# Voice_Interaction_Hat_for_raspberry_pi_v.net
KiCad netlist of a schematic drawn in EAGLE
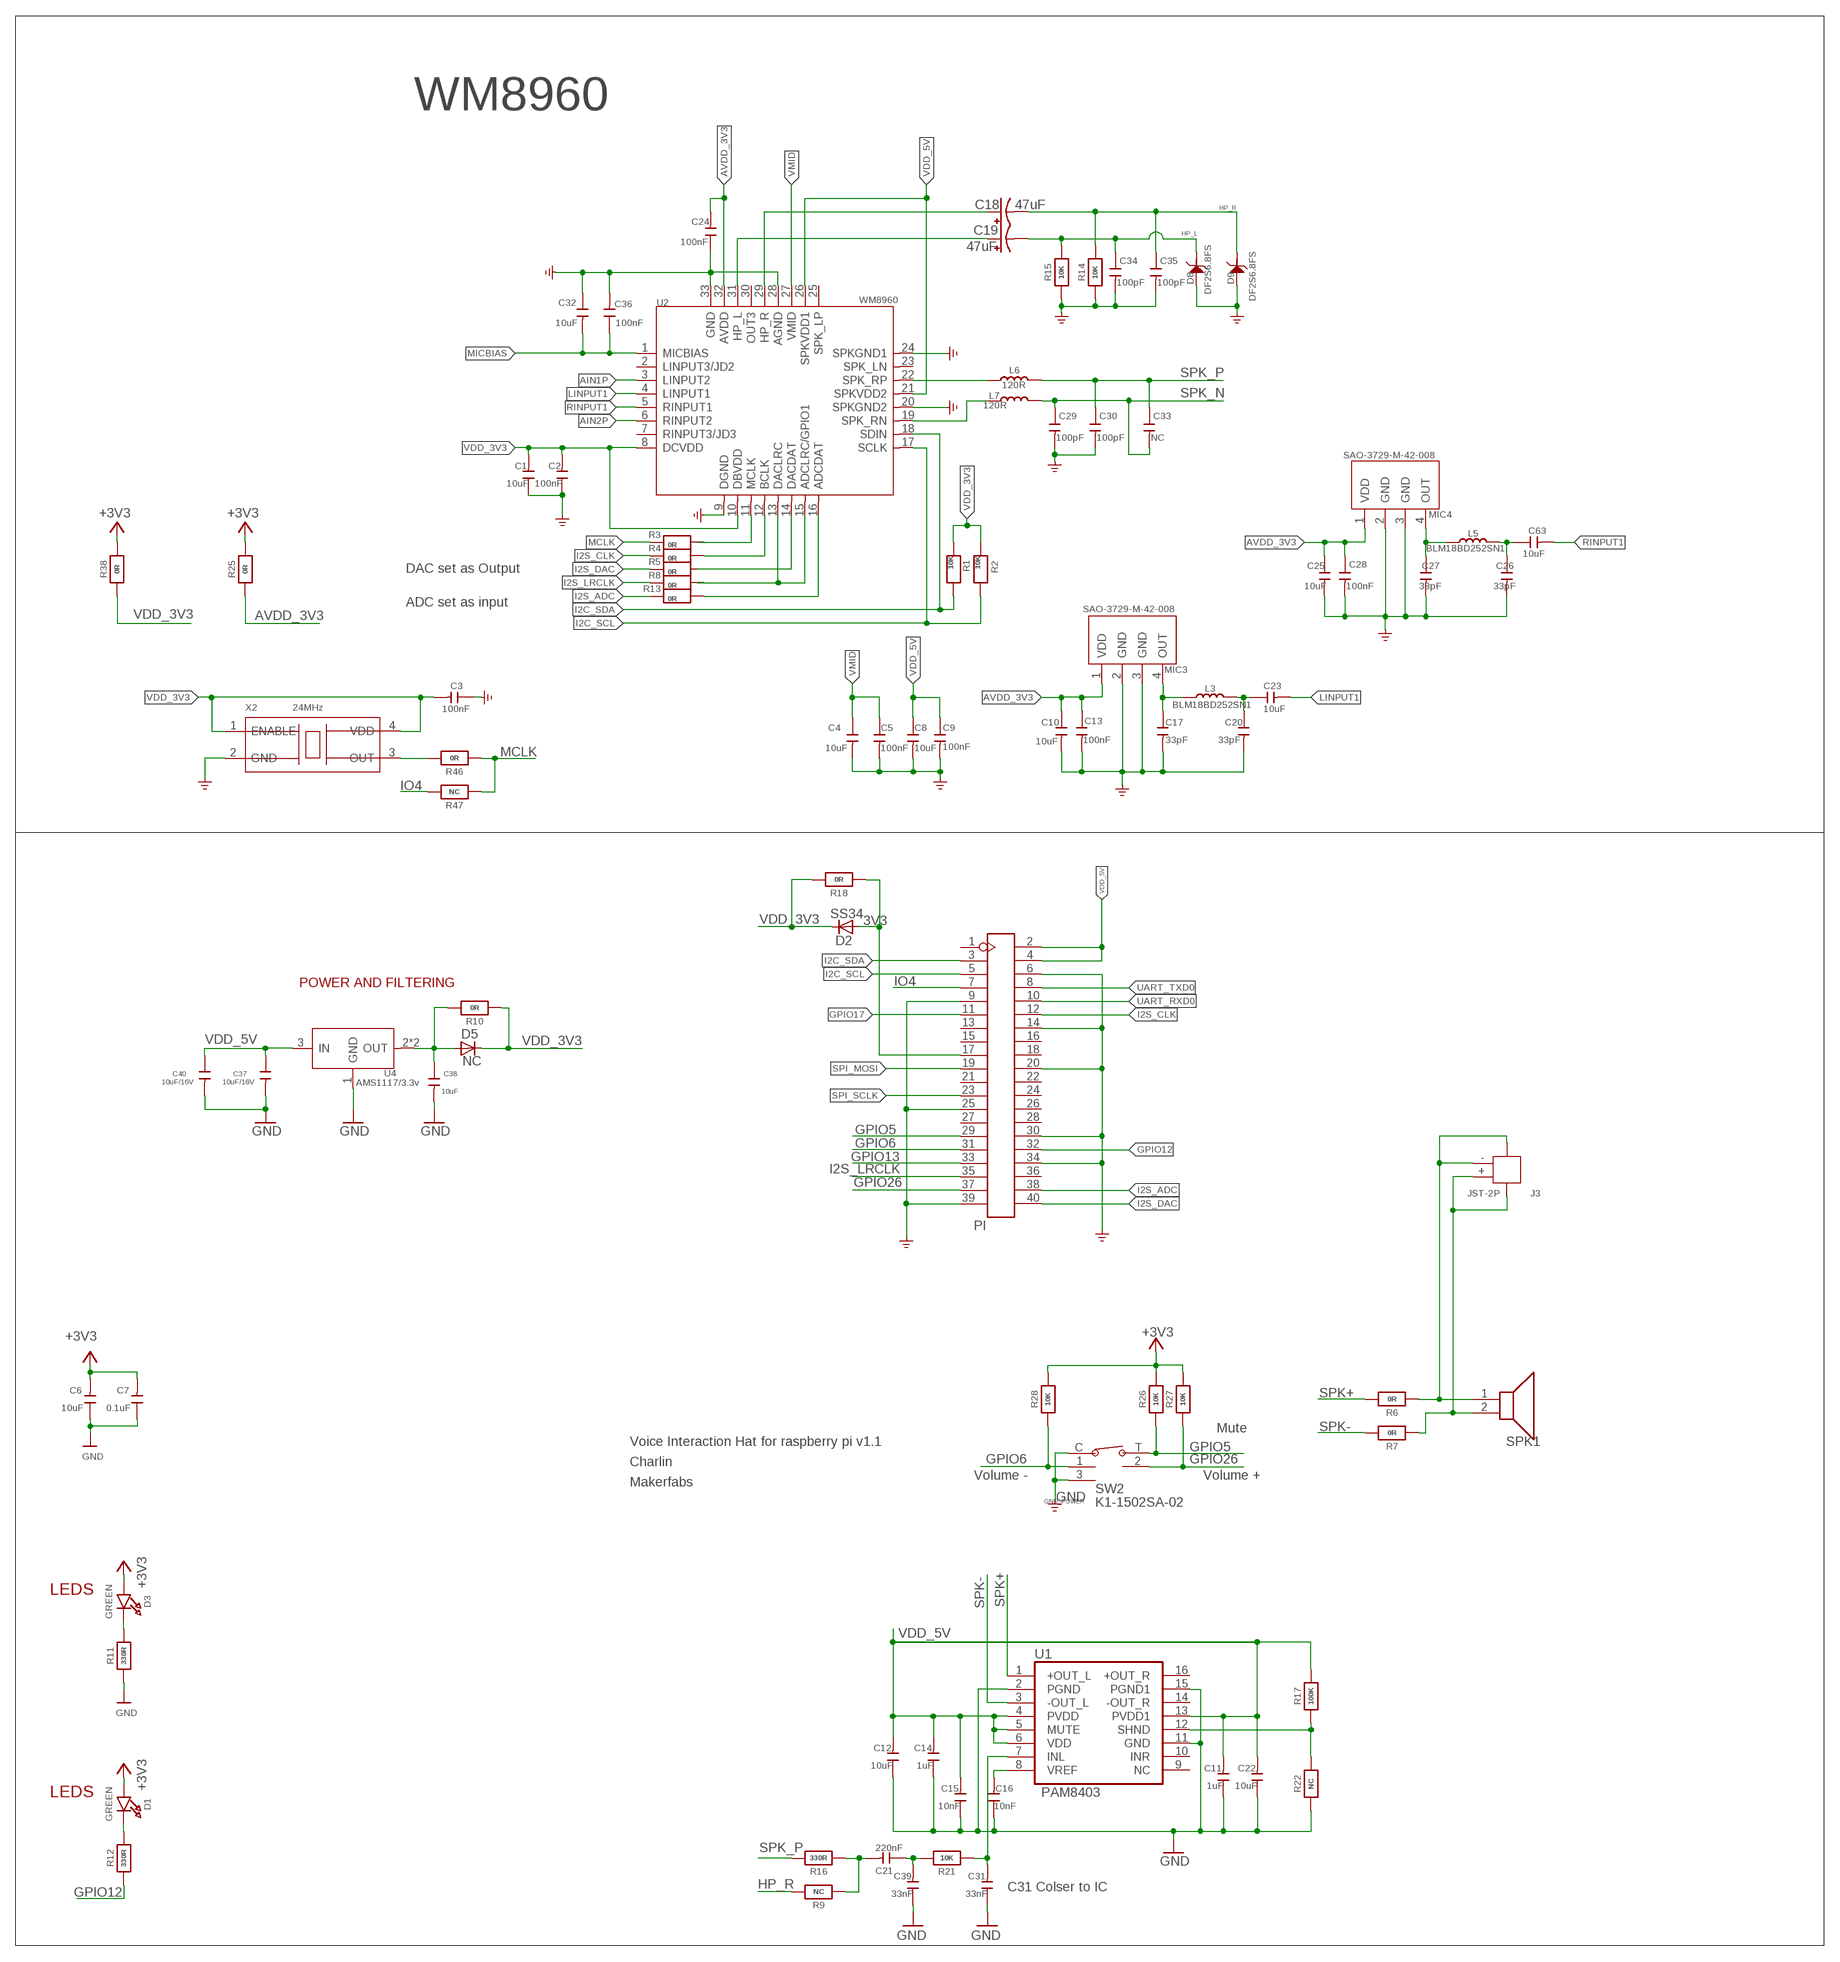
[diagram p0: schematic, sheet 1]

(export (version "E")
  (design (tool "Eeschema 10.0.6"))
  (components
    (comp (ref "C1")
      (value "10uF")
      (footprint "eagle-import:DISCRETE_C0603")
      (libsource (lib "eagle-import") (part "DISCRETE_C-0603"))
    )
    (comp (ref "C2")
      (value "100nF")
      (footprint "eagle-import:DISCRETE_C0603")
      (libsource (lib "eagle-import") (part "DISCRETE_C-0603"))
    )
    (comp (ref "C3")
      (value "100nF")
      (footprint "eagle-import:DISCRETE_C0603")
      (libsource (lib "eagle-import") (part "DISCRETE_C-0603"))
    )
    (comp (ref "C4")
      (value "10uF")
      (footprint "eagle-import:C0603")
      (libsource (lib "eagle-import") (part "CAP-0603"))
    )
    (comp (ref "C5")
      (value "100nF")
      (footprint "eagle-import:C0603")
      (libsource (lib "eagle-import") (part "CAP-0603"))
    )
    (comp (ref "C6")
      (value "10uF")
      (footprint "eagle-import:DISCRETE_C0603")
      (libsource (lib "eagle-import") (part "DISCRETE_C-0603"))
    )
    (comp (ref "C7")
      (value "0.1uF")
      (footprint "eagle-import:DISCRETE_C0603")
      (libsource (lib "eagle-import") (part "DISCRETE_C-0603"))
    )
    (comp (ref "C8")
      (value "10uF")
      (footprint "eagle-import:C0603")
      (libsource (lib "eagle-import") (part "CAP-0603"))
    )
    (comp (ref "C9")
      (value "100nF")
      (footprint "eagle-import:C0603")
      (libsource (lib "eagle-import") (part "CAP-0603"))
    )
    (comp (ref "C10")
      (value "10uF")
      (footprint "eagle-import:C0603")
      (libsource (lib "eagle-import") (part "CAP-0603"))
    )
    (comp (ref "C11")
      (value "1uF")
      (footprint "eagle-import:DISCRETE_C0603")
      (libsource (lib "eagle-import") (part "DISCRETE_C-0603"))
    )
    (comp (ref "C12")
      (value "10uF")
      (footprint "eagle-import:DISCRETE_C0603")
      (libsource (lib "eagle-import") (part "DISCRETE_C-0603"))
    )
    (comp (ref "C13")
      (value "100nF")
      (footprint "eagle-import:C0603")
      (libsource (lib "eagle-import") (part "CAP-0603"))
    )
    (comp (ref "C14")
      (value "1uF")
      (footprint "eagle-import:DISCRETE_C0603")
      (libsource (lib "eagle-import") (part "DISCRETE_C-0603"))
    )
    (comp (ref "C15")
      (value "10nF")
      (footprint "eagle-import:DISCRETE_C0603")
      (libsource (lib "eagle-import") (part "DISCRETE_C-0603"))
    )
    (comp (ref "C16")
      (value "10nF")
      (footprint "eagle-import:DISCRETE_C0603")
      (libsource (lib "eagle-import") (part "DISCRETE_C-0603"))
    )
    (comp (ref "C17")
      (value "33pF")
      (footprint "eagle-import:C0603")
      (libsource (lib "eagle-import") (part "CAP-0603"))
    )
    (comp (ref "C18")
      (value "47uF")
      (footprint "eagle-import:EIA3528")
      (libsource (lib "eagle-import") (part "47UF-POLAR-EIA3528-10V-10%"))
    )
    (comp (ref "C19")
      (value "47uF")
      (footprint "eagle-import:EIA3528")
      (libsource (lib "eagle-import") (part "47UF-POLAR-EIA3528-10V-10%"))
    )
    (comp (ref "C20")
      (value "33pF")
      (footprint "eagle-import:C0603")
      (libsource (lib "eagle-import") (part "CAP-0603"))
    )
    (comp (ref "C21")
      (value "220nF")
      (footprint "eagle-import:DISCRETE_C0603")
      (libsource (lib "eagle-import") (part "DISCRETE_C-0603"))
    )
    (comp (ref "C22")
      (value "10uF")
      (footprint "eagle-import:DISCRETE_C0603")
      (libsource (lib "eagle-import") (part "DISCRETE_C-0603"))
    )
    (comp (ref "C23")
      (value "10uF")
      (footprint "eagle-import:C0603")
      (libsource (lib "eagle-import") (part "CAP-0603"))
    )
    (comp (ref "C24")
      (value "100nF")
      (footprint "eagle-import:DISCRETE_C0603")
      (libsource (lib "eagle-import") (part "DISCRETE_C-0603"))
    )
    (comp (ref "C25")
      (value "10uF")
      (footprint "eagle-import:C0603")
      (libsource (lib "eagle-import") (part "CAP-0603"))
    )
    (comp (ref "C26")
      (value "33pF")
      (footprint "eagle-import:C0603")
      (libsource (lib "eagle-import") (part "CAP-0603"))
    )
    (comp (ref "C27")
      (value "33pF")
      (footprint "eagle-import:C0603")
      (libsource (lib "eagle-import") (part "CAP-0603"))
    )
    (comp (ref "C28")
      (value "100nF")
      (footprint "eagle-import:C0603")
      (libsource (lib "eagle-import") (part "CAP-0603"))
    )
    (comp (ref "C29")
      (value "100pF")
      (footprint "eagle-import:C0603")
      (libsource (lib "eagle-import") (part "CAP-0603"))
    )
    (comp (ref "C30")
      (value "100pF")
      (footprint "eagle-import:C0603")
      (libsource (lib "eagle-import") (part "CAP-0603"))
    )
    (comp (ref "C31")
      (value "33nF")
      (footprint "eagle-import:DISCRETE_C0603")
      (libsource (lib "eagle-import") (part "DISCRETE_C-0603"))
    )
    (comp (ref "C32")
      (value "10uF")
      (footprint "eagle-import:C0603")
      (libsource (lib "eagle-import") (part "CAP-0603"))
    )
    (comp (ref "C33")
      (value "NC")
      (footprint "eagle-import:C0603")
      (libsource (lib "eagle-import") (part "CAP-0603"))
    )
    (comp (ref "C34")
      (value "100pF")
      (footprint "eagle-import:C0603")
      (libsource (lib "eagle-import") (part "CAP-0603"))
    )
    (comp (ref "C35")
      (value "100pF")
      (footprint "eagle-import:C0603")
      (libsource (lib "eagle-import") (part "CAP-0603"))
    )
    (comp (ref "C36")
      (value "100nF")
      (footprint "eagle-import:DISCRETE_C0603")
      (libsource (lib "eagle-import") (part "DISCRETE_C-0603"))
    )
    (comp (ref "C37")
      (value "10uF/16V")
      (footprint "eagle-import:0603")
      (libsource (lib "eagle-import") (part "C-0603"))
    )
    (comp (ref "C38")
      (value "10uF")
      (footprint "eagle-import:0603")
      (libsource (lib "eagle-import") (part "C-0603"))
    )
    (comp (ref "C39")
      (value "33nF")
      (footprint "eagle-import:DISCRETE_C0603")
      (libsource (lib "eagle-import") (part "DISCRETE_C-0603"))
    )
    (comp (ref "C40")
      (value "10uF/16V")
      (footprint "eagle-import:0603")
      (libsource (lib "eagle-import") (part "C-0603"))
    )
    (comp (ref "C63")
      (value "10uF")
      (footprint "eagle-import:C0603")
      (libsource (lib "eagle-import") (part "CAP-0603"))
    )
    (comp (ref "D1")
      (value "GREEN")
      (footprint "eagle-import:CHIPLED_0805_NOOUTLINE")
      (libsource (lib "eagle-import") (part "LED0805_NOOUTLINE"))
    )
    (comp (ref "D2")
      (value "SS34")
      (footprint "eagle-import:DO-214AC")
      (libsource (lib "eagle-import") (part "DIODE-DO-214AC"))
    )
    (comp (ref "D3")
      (value "GREEN")
      (footprint "eagle-import:CHIPLED_0805_NOOUTLINE")
      (libsource (lib "eagle-import") (part "LED0805_NOOUTLINE"))
    )
    (comp (ref "D5")
      (value "NC")
      (footprint "eagle-import:DO-214AC")
      (libsource (lib "eagle-import") (part "DIODE-DO-214AC"))
    )
    (comp (ref "D8")
      (value "DF2S6.8FS")
      (footprint "eagle-import:SOD-923")
      (libsource (lib "eagle-import") (part "D-ESD-2P'DF2S6.8FS'"))
    )
    (comp (ref "D9")
      (value "DF2S6.8FS")
      (footprint "eagle-import:SOD-923")
      (libsource (lib "eagle-import") (part "D-ESD-2P'DF2S6.8FS'"))
    )
    (comp (ref "J3")
      (value "JST-2P")
      (footprint "eagle-import:HW2-SMD-2.0-90D")
      (libsource (lib "eagle-import") (part "JST-2P-SMD'2.0'"))
    )
    (comp (ref "L3")
      (value "BLM18BD252SN1")
      (footprint "eagle-import:L0603")
      (libsource (lib "eagle-import") (part "INDUCTOR/FERRITE-BEAD'0603'"))
    )
    (comp (ref "L5")
      (value "BLM18BD252SN1")
      (footprint "eagle-import:L0603")
      (libsource (lib "eagle-import") (part "INDUCTOR/FERRITE-BEAD'0603'"))
    )
    (comp (ref "L6")
      (value "120R")
      (footprint "eagle-import:L0603")
      (libsource (lib "eagle-import") (part "INDUCTOR/FERRITE-BEAD'0603'"))
    )
    (comp (ref "L7")
      (value "120R")
      (footprint "eagle-import:L0603")
      (libsource (lib "eagle-import") (part "INDUCTOR/FERRITE-BEAD'0603'"))
    )
    (comp (ref "MIC3")
      (value "SAO-3729-M-42-008")
      (footprint "eagle-import:MIC4-SMD-3.76X2.95MM")
      (libsource (lib "eagle-import") (part "MIC-MSM421A3729H8-C"))
    )
    (comp (ref "MIC4")
      (value "SAO-3729-M-42-008")
      (footprint "eagle-import:MIC4-SMD-3.76X2.95MM")
      (libsource (lib "eagle-import") (part "MIC-MSM421A3729H8-C"))
    )
    (comp (ref "PI")
      (value "HEADER-2X20P1")
      (footprint "eagle-import:DIP-2X20-2.54MM")
      (libsource (lib "eagle-import") (part "HEADER-2X20P1"))
    )
    (comp (ref "R1")
      (value "10K")
      (footprint "eagle-import:0603-NO")
      (libsource (lib "eagle-import") (part "RESISTOR_0603_NOOUT"))
    )
    (comp (ref "R2")
      (value "10K")
      (footprint "eagle-import:0603-NO")
      (libsource (lib "eagle-import") (part "RESISTOR_0603_NOOUT"))
    )
    (comp (ref "R3")
      (value "0R")
      (footprint "eagle-import:0603-NO")
      (libsource (lib "eagle-import") (part "RESISTOR_0603_NOOUT"))
    )
    (comp (ref "R4")
      (value "0R")
      (footprint "eagle-import:0603-NO")
      (libsource (lib "eagle-import") (part "RESISTOR_0603_NOOUT"))
    )
    (comp (ref "R5")
      (value "0R")
      (footprint "eagle-import:0603-NO")
      (libsource (lib "eagle-import") (part "RESISTOR_0603_NOOUT"))
    )
    (comp (ref "R6")
      (value "0R")
      (footprint "eagle-import:0603-NO")
      (libsource (lib "eagle-import") (part "RESISTOR_0603_NOOUT"))
    )
    (comp (ref "R7")
      (value "0R")
      (footprint "eagle-import:0603-NO")
      (libsource (lib "eagle-import") (part "RESISTOR_0603_NOOUT"))
    )
    (comp (ref "R8")
      (value "0R")
      (footprint "eagle-import:0603-NO")
      (libsource (lib "eagle-import") (part "RESISTOR_0603_NOOUT"))
    )
    (comp (ref "R9")
      (value "NC")
      (footprint "eagle-import:0603-NO")
      (libsource (lib "eagle-import") (part "RESISTOR_0603_NOOUT"))
    )
    (comp (ref "R10")
      (value "0R")
      (footprint "eagle-import:0603-NO")
      (libsource (lib "eagle-import") (part "RESISTOR_0603_NOOUT"))
    )
    (comp (ref "R11")
      (value "330R")
      (footprint "eagle-import:0603-NO")
      (libsource (lib "eagle-import") (part "RESISTOR_0603_NOOUT"))
    )
    (comp (ref "R12")
      (value "330R")
      (footprint "eagle-import:0603-NO")
      (libsource (lib "eagle-import") (part "RESISTOR_0603_NOOUT"))
    )
    (comp (ref "R13")
      (value "0R")
      (footprint "eagle-import:0603-NO")
      (libsource (lib "eagle-import") (part "RESISTOR_0603_NOOUT"))
    )
    (comp (ref "R14")
      (value "10K")
      (footprint "eagle-import:0603-NO")
      (libsource (lib "eagle-import") (part "RESISTOR_0603_NOOUT"))
    )
    (comp (ref "R15")
      (value "10K")
      (footprint "eagle-import:0603-NO")
      (libsource (lib "eagle-import") (part "RESISTOR_0603_NOOUT"))
    )
    (comp (ref "R16")
      (value "330R")
      (footprint "eagle-import:0603-NO")
      (libsource (lib "eagle-import") (part "RESISTOR_0603_NOOUT"))
    )
    (comp (ref "R17")
      (value "100K")
      (footprint "eagle-import:0603-NO")
      (libsource (lib "eagle-import") (part "RESISTOR_0603_NOOUT"))
    )
    (comp (ref "R18")
      (value "0R")
      (footprint "eagle-import:0603-NO")
      (libsource (lib "eagle-import") (part "RESISTOR_0603_NOOUT"))
    )
    (comp (ref "R21")
      (value "10K")
      (footprint "eagle-import:0603-NO")
      (libsource (lib "eagle-import") (part "RESISTOR_0603_NOOUT"))
    )
    (comp (ref "R22")
      (value "NC")
      (footprint "eagle-import:0603-NO")
      (libsource (lib "eagle-import") (part "RESISTOR_0603_NOOUT"))
    )
    (comp (ref "R25")
      (value "0R")
      (footprint "eagle-import:0603-NO")
      (libsource (lib "eagle-import") (part "RESISTOR_0603_NOOUT"))
    )
    (comp (ref "R26")
      (value "10K")
      (footprint "eagle-import:0603-NO")
      (libsource (lib "eagle-import") (part "RESISTOR_0603_NOOUT"))
    )
    (comp (ref "R27")
      (value "10K")
      (footprint "eagle-import:0603-NO")
      (libsource (lib "eagle-import") (part "RESISTOR_0603_NOOUT"))
    )
    (comp (ref "R28")
      (value "10K")
      (footprint "eagle-import:0603-NO")
      (libsource (lib "eagle-import") (part "RESISTOR_0603_NOOUT"))
    )
    (comp (ref "R38")
      (value "0R")
      (footprint "eagle-import:0603-NO")
      (libsource (lib "eagle-import") (part "RESISTOR_0603_NOOUT"))
    )
    (comp (ref "R46")
      (value "0R")
      (footprint "eagle-import:0603-NO")
      (libsource (lib "eagle-import") (part "RESISTOR_0603_NOOUT"))
    )
    (comp (ref "R47")
      (value "NC")
      (footprint "eagle-import:0603-NO")
      (libsource (lib "eagle-import") (part "RESISTOR_0603_NOOUT"))
    )
    (comp (ref "SPK1")
      (value "SPK")
      (footprint "eagle-import:SPK-SMD2-5000L3000W")
      (libsource (lib "eagle-import") (part "SPK"))
    )
    (comp (ref "SW2")
      (value "K1-1502SA-02")
      (footprint "eagle-import:SMD5-60P-1180L1170W")
      (libsource (lib "eagle-import") (part "K1-1502SA-02"))
    )
    (comp (ref "U1")
      (value "PAM8403")
      (footprint "eagle-import:SOP-16")
      (libsource (lib "eagle-import") (part "PAM8403"))
    )
    (comp (ref "U2")
      (value "WM8960")
      (footprint "eagle-import:QFN32G-0.5-5X5MM")
      (libsource (lib "eagle-import") (part "AMPLIFIER-WM8960"))
    )
    (comp (ref "U4")
      (value "AMS1117/3.3v")
      (footprint "eagle-import:SOT89")
      (libsource (lib "eagle-import") (part "LD1117'SOT89'"))
    )
    (comp (ref "X2")
      (value "24MHz")
      (footprint "eagle-import:OSC4-SMD-2.5X2.0X0.8MM")
      (libsource (lib "eagle-import") (part "CRYSTAL-OSCILLATOR2.52.0"))
    )
  )
  (nets
    (net (code "1") (name "+3V3") (class "Default")
      (node (ref "C6") (pin "2") (pinfunction "2_2") (pintype "passive"))
      (node (ref "C7") (pin "2") (pinfunction "2_2") (pintype "passive"))
      (node (ref "D1") (pin "A") (pinfunction "A_A") (pintype "passive"))
      (node (ref "D3") (pin "A") (pinfunction "A_A") (pintype "passive"))
      (node (ref "R25") (pin "2") (pinfunction "2_2") (pintype "passive"))
      (node (ref "R26") (pin "2") (pinfunction "2_2") (pintype "passive"))
      (node (ref "R27") (pin "2") (pinfunction "2_2") (pintype "passive"))
      (node (ref "R28") (pin "2") (pinfunction "2_2") (pintype "passive"))
      (node (ref "R38") (pin "2") (pinfunction "2_2") (pintype "passive"))
    )
    (net (code "2") (name "/3V3") (class "Default")
      (node (ref "D2") (pin "A") (pinfunction "A_A") (pintype "passive"))
      (node (ref "PI") (pin "17") (pinfunction "17_17") (pintype "bidirectional"))
      (node (ref "R18") (pin "1") (pinfunction "1_1") (pintype "passive"))
    )
    (net (code "3") (name "/GPIO5") (class "Default")
      (node (ref "PI") (pin "29") (pinfunction "29_29") (pintype "bidirectional"))
      (node (ref "R26") (pin "1") (pinfunction "1_1") (pintype "passive"))
      (node (ref "SW2") (pin "T") (pinfunction "T_T") (pintype "bidirectional"))
    )
    (net (code "4") (name "/GPIO6") (class "Default")
      (node (ref "PI") (pin "31") (pinfunction "31_31") (pintype "bidirectional"))
      (node (ref "R28") (pin "1") (pinfunction "1_1") (pintype "passive"))
      (node (ref "SW2") (pin "1") (pinfunction "1_1") (pintype "bidirectional"))
    )
    (net (code "5") (name "/GPIO13") (class "Default")
      (node (ref "PI") (pin "33") (pinfunction "33_33") (pintype "bidirectional"))
    )
    (net (code "6") (name "/GPIO26") (class "Default")
      (node (ref "PI") (pin "37") (pinfunction "37_37") (pintype "bidirectional"))
      (node (ref "R27") (pin "1") (pinfunction "1_1") (pintype "passive"))
      (node (ref "SW2") (pin "2") (pinfunction "2_2") (pintype "bidirectional"))
    )
    (net (code "7") (name "/HP_L") (class "Default")
      (node (ref "C19") (pin "C") (pinfunction "-_C") (pintype "passive"))
      (node (ref "C34") (pin "1") (pinfunction "1_1") (pintype "passive"))
      (node (ref "D8") (pin "1") (pinfunction "2_1") (pintype "bidirectional"))
      (node (ref "R15") (pin "2") (pinfunction "2_2") (pintype "passive"))
    )
    (net (code "8") (name "/HP_R") (class "Default")
      (node (ref "C18") (pin "C") (pinfunction "-_C") (pintype "passive"))
      (node (ref "C35") (pin "1") (pinfunction "1_1") (pintype "passive"))
      (node (ref "D9") (pin "1") (pinfunction "2_1") (pintype "bidirectional"))
      (node (ref "R14") (pin "2") (pinfunction "2_2") (pintype "passive"))
      (node (ref "R9") (pin "2") (pinfunction "2_2") (pintype "passive"))
    )
    (net (code "9") (name "/IO4") (class "Default")
      (node (ref "PI") (pin "7") (pinfunction "7_7") (pintype "bidirectional"))
      (node (ref "R47") (pin "2") (pinfunction "2_2") (pintype "passive"))
    )
    (net (code "10") (name "/SPK+") (class "Default")
      (node (ref "R6") (pin "2") (pinfunction "2_2") (pintype "passive"))
      (node (ref "U1") (pin "1") (pinfunction "+OUT_L_1") (pintype "input"))
    )
    (net (code "11") (name "/SPK-") (class "Default")
      (node (ref "R7") (pin "2") (pinfunction "2_2") (pintype "passive"))
      (node (ref "U1") (pin "3") (pinfunction "-OUT_L_3") (pintype "input"))
    )
    (net (code "12") (name "/SPK_N") (class "Default")
      (node (ref "C29") (pin "1") (pinfunction "1_1") (pintype "passive"))
      (node (ref "C33") (pin "2") (pinfunction "2_2") (pintype "passive"))
      (node (ref "L7") (pin "2") (pinfunction "2_2") (pintype "passive"))
    )
    (net (code "13") (name "/SPK_P") (class "Default")
      (node (ref "C30") (pin "1") (pinfunction "1_1") (pintype "passive"))
      (node (ref "C33") (pin "1") (pinfunction "1_1") (pintype "passive"))
      (node (ref "L6") (pin "2") (pinfunction "2_2") (pintype "passive"))
      (node (ref "R16") (pin "2") (pinfunction "2_2") (pintype "passive"))
    )
    (net (code "14") (name "AIN1P") (class "Default")
      (node (ref "U2") (pin "3") (pinfunction "LINPUT2_3") (pintype "bidirectional"))
    )
    (net (code "15") (name "AIN2P") (class "Default")
      (node (ref "U2") (pin "6") (pinfunction "RINPUT2_6") (pintype "bidirectional"))
    )
    (net (code "16") (name "AVDD_3V3") (class "Default")
      (node (ref "C10") (pin "1") (pinfunction "1_1") (pintype "passive"))
      (node (ref "C13") (pin "1") (pinfunction "1_1") (pintype "passive"))
      (node (ref "C24") (pin "2") (pinfunction "2_2") (pintype "passive"))
      (node (ref "C25") (pin "1") (pinfunction "1_1") (pintype "passive"))
      (node (ref "C28") (pin "1") (pinfunction "1_1") (pintype "passive"))
      (node (ref "MIC3") (pin "1") (pinfunction "VDD_1") (pintype "bidirectional"))
      (node (ref "MIC4") (pin "1") (pinfunction "VDD_1") (pintype "bidirectional"))
      (node (ref "R25") (pin "1") (pinfunction "1_1") (pintype "passive"))
      (node (ref "U2") (pin "32") (pinfunction "AVDD_32") (pintype "bidirectional"))
    )
    (net (code "17") (name "GND") (class "Default")
      (node (ref "C1") (pin "1") (pinfunction "1_1") (pintype "passive"))
      (node (ref "C10") (pin "2") (pinfunction "2_2") (pintype "passive"))
      (node (ref "C11") (pin "1") (pinfunction "1_1") (pintype "passive"))
      (node (ref "C12") (pin "1") (pinfunction "1_1") (pintype "passive"))
      (node (ref "C13") (pin "2") (pinfunction "2_2") (pintype "passive"))
      (node (ref "C14") (pin "1") (pinfunction "1_1") (pintype "passive"))
      (node (ref "C15") (pin "1") (pinfunction "1_1") (pintype "passive"))
      (node (ref "C16") (pin "1") (pinfunction "1_1") (pintype "passive"))
      (node (ref "C17") (pin "2") (pinfunction "2_2") (pintype "passive"))
      (node (ref "C2") (pin "1") (pinfunction "1_1") (pintype "passive"))
      (node (ref "C20") (pin "2") (pinfunction "2_2") (pintype "passive"))
      (node (ref "C22") (pin "1") (pinfunction "1_1") (pintype "passive"))
      (node (ref "C24") (pin "1") (pinfunction "1_1") (pintype "passive"))
      (node (ref "C25") (pin "2") (pinfunction "2_2") (pintype "passive"))
      (node (ref "C26") (pin "2") (pinfunction "2_2") (pintype "passive"))
      (node (ref "C27") (pin "2") (pinfunction "2_2") (pintype "passive"))
      (node (ref "C28") (pin "2") (pinfunction "2_2") (pintype "passive"))
      (node (ref "C29") (pin "2") (pinfunction "2_2") (pintype "passive"))
      (node (ref "C3") (pin "1") (pinfunction "1_1") (pintype "passive"))
      (node (ref "C30") (pin "2") (pinfunction "2_2") (pintype "passive"))
      (node (ref "C31") (pin "1") (pinfunction "1_1") (pintype "passive"))
      (node (ref "C32") (pin "1") (pinfunction "1_1") (pintype "passive"))
      (node (ref "C34") (pin "2") (pinfunction "2_2") (pintype "passive"))
      (node (ref "C35") (pin "2") (pinfunction "2_2") (pintype "passive"))
      (node (ref "C36") (pin "2") (pinfunction "2_2") (pintype "passive"))
      (node (ref "C37") (pin "2") (pinfunction "2_2") (pintype "passive"))
      (node (ref "C38") (pin "2") (pinfunction "2_2") (pintype "passive"))
      (node (ref "C39") (pin "1") (pinfunction "1_1") (pintype "passive"))
      (node (ref "C4") (pin "2") (pinfunction "2_2") (pintype "passive"))
      (node (ref "C40") (pin "2") (pinfunction "2_2") (pintype "passive"))
      (node (ref "C5") (pin "2") (pinfunction "2_2") (pintype "passive"))
      (node (ref "C6") (pin "1") (pinfunction "1_1") (pintype "passive"))
      (node (ref "C7") (pin "1") (pinfunction "1_1") (pintype "passive"))
      (node (ref "C8") (pin "2") (pinfunction "2_2") (pintype "passive"))
      (node (ref "C9") (pin "2") (pinfunction "2_2") (pintype "passive"))
      (node (ref "D8") (pin "2") (pinfunction "1_2") (pintype "bidirectional"))
      (node (ref "D9") (pin "2") (pinfunction "1_2") (pintype "bidirectional"))
      (node (ref "MIC3") (pin "2") (pinfunction "GND_2") (pintype "bidirectional"))
      (node (ref "MIC3") (pin "3") (pinfunction "GND_3") (pintype "bidirectional"))
      (node (ref "MIC4") (pin "2") (pinfunction "GND_2") (pintype "bidirectional"))
      (node (ref "MIC4") (pin "3") (pinfunction "GND_3") (pintype "bidirectional"))
      (node (ref "PI") (pin "14") (pinfunction "14_14") (pintype "bidirectional"))
      (node (ref "PI") (pin "20") (pinfunction "20_20") (pintype "bidirectional"))
      (node (ref "PI") (pin "25") (pinfunction "25_25") (pintype "bidirectional"))
      (node (ref "PI") (pin "30") (pinfunction "30_30") (pintype "bidirectional"))
      (node (ref "PI") (pin "34") (pinfunction "34_34") (pintype "bidirectional"))
      (node (ref "PI") (pin "39") (pinfunction "39_39") (pintype "bidirectional"))
      (node (ref "PI") (pin "6") (pinfunction "6_6") (pintype "bidirectional"))
      (node (ref "PI") (pin "9") (pinfunction "9_9") (pintype "bidirectional"))
      (node (ref "R11") (pin "1") (pinfunction "1_1") (pintype "passive"))
      (node (ref "R14") (pin "1") (pinfunction "1_1") (pintype "passive"))
      (node (ref "R15") (pin "1") (pinfunction "1_1") (pintype "passive"))
      (node (ref "R22") (pin "1") (pinfunction "1_1") (pintype "passive"))
      (node (ref "SW2") (pin "3") (pinfunction "3_3") (pintype "bidirectional"))
      (node (ref "SW2") (pin "C") (pinfunction "C_C") (pintype "bidirectional"))
      (node (ref "U1") (pin "11") (pinfunction "GND_11") (pintype "output"))
      (node (ref "U1") (pin "15") (pinfunction "PGND1_15") (pintype "output"))
      (node (ref "U1") (pin "2") (pinfunction "PGND_2") (pintype "input"))
      (node (ref "U2") (pin "20") (pinfunction "SPKGND2_20") (pintype "bidirectional"))
      (node (ref "U2") (pin "24") (pinfunction "SPKGND1_24") (pintype "bidirectional"))
      (node (ref "U2") (pin "28") (pinfunction "AGND_28") (pintype "bidirectional"))
      (node (ref "U2") (pin "33") (pinfunction "GND_33") (pintype "bidirectional"))
      (node (ref "U2") (pin "9") (pinfunction "DGND_9") (pintype "bidirectional"))
      (node (ref "U4") (pin "1") (pinfunction "GND_1") (pintype "bidirectional"))
      (node (ref "X2") (pin "2") (pinfunction "GND_2") (pintype "bidirectional"))
    )
    (net (code "18") (name "GPIO12") (class "Default")
      (node (ref "PI") (pin "32") (pinfunction "32_32") (pintype "bidirectional"))
      (node (ref "R12") (pin "1") (pinfunction "1_1") (pintype "passive"))
    )
    (net (code "19") (name "GPIO17") (class "Default")
      (node (ref "PI") (pin "11") (pinfunction "11_11") (pintype "bidirectional"))
    )
    (net (code "20") (name "I2C_SCL") (class "Default")
      (node (ref "PI") (pin "5") (pinfunction "5_5") (pintype "bidirectional"))
      (node (ref "R2") (pin "1") (pinfunction "1_1") (pintype "passive"))
      (node (ref "U2") (pin "17") (pinfunction "SCLK_17") (pintype "bidirectional"))
    )
    (net (code "21") (name "I2C_SDA") (class "Default")
      (node (ref "PI") (pin "3") (pinfunction "3_3") (pintype "bidirectional"))
      (node (ref "R1") (pin "1") (pinfunction "1_1") (pintype "passive"))
      (node (ref "U2") (pin "18") (pinfunction "SDIN_18") (pintype "bidirectional"))
    )
    (net (code "22") (name "I2S_ADC") (class "Default")
      (node (ref "PI") (pin "38") (pinfunction "38_38") (pintype "bidirectional"))
      (node (ref "R13") (pin "2") (pinfunction "2_2") (pintype "passive"))
    )
    (net (code "23") (name "I2S_CLK") (class "Default")
      (node (ref "PI") (pin "12") (pinfunction "12_12") (pintype "bidirectional"))
      (node (ref "R4") (pin "2") (pinfunction "2_2") (pintype "passive"))
    )
    (net (code "24") (name "I2S_DAC") (class "Default")
      (node (ref "PI") (pin "40") (pinfunction "40_40") (pintype "bidirectional"))
      (node (ref "R5") (pin "2") (pinfunction "2_2") (pintype "passive"))
    )
    (net (code "25") (name "I2S_LRCLK") (class "Default")
      (node (ref "PI") (pin "35") (pinfunction "35_35") (pintype "bidirectional"))
      (node (ref "R8") (pin "2") (pinfunction "2_2") (pintype "passive"))
    )
    (net (code "26") (name "LINPUT1") (class "Default")
      (node (ref "C23") (pin "2") (pinfunction "2_2") (pintype "passive"))
      (node (ref "U2") (pin "4") (pinfunction "LINPUT1_4") (pintype "bidirectional"))
    )
    (net (code "27") (name "MCLK") (class "Default")
      (node (ref "R3") (pin "2") (pinfunction "2_2") (pintype "passive"))
      (node (ref "R46") (pin "1") (pinfunction "1_1") (pintype "passive"))
      (node (ref "R47") (pin "1") (pinfunction "1_1") (pintype "passive"))
    )
    (net (code "28") (name "MICBIAS") (class "Default")
      (node (ref "C32") (pin "2") (pinfunction "2_2") (pintype "passive"))
      (node (ref "C36") (pin "1") (pinfunction "1_1") (pintype "passive"))
      (node (ref "U2") (pin "1") (pinfunction "MICBIAS_1") (pintype "bidirectional"))
    )
    (net (code "29") (name "Net-(C18-+)") (class "Default")
      (node (ref "C18") (pin "A") (pinfunction "+_A") (pintype "passive"))
      (node (ref "U2") (pin "29") (pinfunction "HP_R_29") (pintype "bidirectional"))
    )
    (net (code "30") (name "Net-(C19-+)") (class "Default")
      (node (ref "C19") (pin "A") (pinfunction "+_A") (pintype "passive"))
      (node (ref "U2") (pin "31") (pinfunction "HP_L_31") (pintype "bidirectional"))
    )
    (net (code "31") (name "Net-(C20-Pad1)") (class "Default")
      (node (ref "C20") (pin "1") (pinfunction "1_1") (pintype "passive"))
      (node (ref "C23") (pin "1") (pinfunction "1_1") (pintype "passive"))
      (node (ref "L3") (pin "2") (pinfunction "2_2") (pintype "passive"))
    )
    (net (code "32") (name "Net-(C21-Pad1)") (class "Default")
      (node (ref "C21") (pin "1") (pinfunction "1_1") (pintype "passive"))
      (node (ref "C39") (pin "2") (pinfunction "2_2") (pintype "passive"))
      (node (ref "R21") (pin "2") (pinfunction "2_2") (pintype "passive"))
    )
    (net (code "33") (name "Net-(C21-Pad2)") (class "Default")
      (node (ref "C21") (pin "2") (pinfunction "2_2") (pintype "passive"))
      (node (ref "R16") (pin "1") (pinfunction "1_1") (pintype "passive"))
      (node (ref "R9") (pin "1") (pinfunction "1_1") (pintype "passive"))
    )
    (net (code "34") (name "Net-(C26-Pad1)") (class "Default")
      (node (ref "C26") (pin "1") (pinfunction "1_1") (pintype "passive"))
      (node (ref "C63") (pin "1") (pinfunction "1_1") (pintype "passive"))
      (node (ref "L5") (pin "2") (pinfunction "2_2") (pintype "passive"))
    )
    (net (code "35") (name "Net-(C38-Pad1)") (class "Default")
      (node (ref "C38") (pin "1") (pinfunction "1_1") (pintype "passive"))
      (node (ref "D5") (pin "A") (pinfunction "A_A") (pintype "passive"))
      (node (ref "R10") (pin "2") (pinfunction "2_2") (pintype "passive"))
      (node (ref "U4") (pin "2") (pinfunction "OUT_2") (pintype "bidirectional"))
      (node (ref "U4") (pin "4") (pinfunction "OUT_4") (pintype "bidirectional"))
    )
    (net (code "36") (name "Net-(D1-PadC)") (class "Default")
      (node (ref "D1") (pin "C") (pinfunction "C_C") (pintype "passive"))
      (node (ref "R12") (pin "2") (pinfunction "2_2") (pintype "passive"))
    )
    (net (code "37") (name "Net-(D3-PadC)") (class "Default")
      (node (ref "D3") (pin "C") (pinfunction "C_C") (pintype "passive"))
      (node (ref "R11") (pin "2") (pinfunction "2_2") (pintype "passive"))
    )
    (net (code "38") (name "Net-(J3-1)") (class "Default")
      (node (ref "J3") (pin "+") (pinfunction "1_+") (pintype "bidirectional"))
      (node (ref "J3") (pin "4") (pinfunction "4_4") (pintype "bidirectional"))
      (node (ref "R7") (pin "1") (pinfunction "1_1") (pintype "passive"))
      (node (ref "SPK1") (pin "2") (pinfunction "P$2_2") (pintype "bidirectional"))
    )
    (net (code "39") (name "Net-(J3-2)") (class "Default")
      (node (ref "J3") (pin "-") (pinfunction "2_-") (pintype "bidirectional"))
      (node (ref "J3") (pin "3") (pinfunction "3_3") (pintype "bidirectional"))
      (node (ref "R6") (pin "1") (pinfunction "1_1") (pintype "passive"))
      (node (ref "SPK1") (pin "1") (pinfunction "P$1_1") (pintype "bidirectional"))
    )
    (net (code "40") (name "Net-(MIC3-OUT)") (class "Default")
      (node (ref "C17") (pin "1") (pinfunction "1_1") (pintype "passive"))
      (node (ref "L3") (pin "1") (pinfunction "1_1") (pintype "passive"))
      (node (ref "MIC3") (pin "4") (pinfunction "OUT_4") (pintype "bidirectional"))
    )
    (net (code "41") (name "Net-(MIC4-OUT)") (class "Default")
      (node (ref "C27") (pin "1") (pinfunction "1_1") (pintype "passive"))
      (node (ref "L5") (pin "1") (pinfunction "1_1") (pintype "passive"))
      (node (ref "MIC4") (pin "4") (pinfunction "OUT_4") (pintype "bidirectional"))
    )
    (net (code "42") (name "Net-(U1-INL)") (class "Default")
      (node (ref "C31") (pin "2") (pinfunction "2_2") (pintype "passive"))
      (node (ref "R21") (pin "1") (pinfunction "1_1") (pintype "passive"))
      (node (ref "U1") (pin "7") (pinfunction "INL_7") (pintype "input"))
    )
    (net (code "43") (name "Net-(U1-SHND)") (class "Default")
      (node (ref "R17") (pin "1") (pinfunction "1_1") (pintype "passive"))
      (node (ref "R22") (pin "2") (pinfunction "2_2") (pintype "passive"))
      (node (ref "U1") (pin "12") (pinfunction "SHND_12") (pintype "output"))
    )
    (net (code "44") (name "Net-(U1-VREF)") (class "Default")
      (node (ref "C16") (pin "2") (pinfunction "2_2") (pintype "passive"))
      (node (ref "U1") (pin "8") (pinfunction "VREF_8") (pintype "input"))
    )
    (net (code "45") (name "Net-(U2-ADCDAT)") (class "Default")
      (node (ref "R13") (pin "1") (pinfunction "1_1") (pintype "passive"))
      (node (ref "U2") (pin "16") (pinfunction "ADCDAT_16") (pintype "bidirectional"))
    )
    (net (code "46") (name "Net-(U2-ADCLRC{slash}GPIO1)") (class "Default")
      (node (ref "R8") (pin "1") (pinfunction "1_1") (pintype "passive"))
      (node (ref "U2") (pin "13") (pinfunction "DACLRC_13") (pintype "bidirectional"))
      (node (ref "U2") (pin "15") (pinfunction "ADCLRC/GPIO1_15") (pintype "bidirectional"))
    )
    (net (code "47") (name "Net-(U2-BCLK)") (class "Default")
      (node (ref "R4") (pin "1") (pinfunction "1_1") (pintype "passive"))
      (node (ref "U2") (pin "12") (pinfunction "BCLK_12") (pintype "bidirectional"))
    )
    (net (code "48") (name "Net-(U2-DACDAT)") (class "Default")
      (node (ref "R5") (pin "1") (pinfunction "1_1") (pintype "passive"))
      (node (ref "U2") (pin "14") (pinfunction "DACDAT_14") (pintype "bidirectional"))
    )
    (net (code "49") (name "Net-(U2-MCLK)") (class "Default")
      (node (ref "R3") (pin "1") (pinfunction "1_1") (pintype "passive"))
      (node (ref "U2") (pin "11") (pinfunction "MCLK_11") (pintype "bidirectional"))
    )
    (net (code "50") (name "Net-(U2-SPK_RN)") (class "Default")
      (node (ref "L7") (pin "1") (pinfunction "1_1") (pintype "passive"))
      (node (ref "U2") (pin "19") (pinfunction "SPK_RN_19") (pintype "bidirectional"))
    )
    (net (code "51") (name "Net-(U2-SPK_RP)") (class "Default")
      (node (ref "L6") (pin "1") (pinfunction "1_1") (pintype "passive"))
      (node (ref "U2") (pin "22") (pinfunction "SPK_RP_22") (pintype "bidirectional"))
    )
    (net (code "52") (name "Net-(X2-OUT)") (class "Default")
      (node (ref "R46") (pin "2") (pinfunction "2_2") (pintype "passive"))
      (node (ref "X2") (pin "3") (pinfunction "OUT_3") (pintype "bidirectional"))
    )
    (net (code "53") (name "RINPUT1") (class "Default")
      (node (ref "C63") (pin "2") (pinfunction "2_2") (pintype "passive"))
      (node (ref "U2") (pin "5") (pinfunction "RINPUT1_5") (pintype "bidirectional"))
    )
    (net (code "54") (name "SPI_MOSI") (class "Default")
      (node (ref "PI") (pin "19") (pinfunction "19_19") (pintype "bidirectional"))
    )
    (net (code "55") (name "SPI_SCLK") (class "Default")
      (node (ref "PI") (pin "23") (pinfunction "23_23") (pintype "bidirectional"))
    )
    (net (code "56") (name "UART_RXD0") (class "Default")
      (node (ref "PI") (pin "10") (pinfunction "10_10") (pintype "bidirectional"))
    )
    (net (code "57") (name "UART_TXD0") (class "Default")
      (node (ref "PI") (pin "8") (pinfunction "8_8") (pintype "bidirectional"))
    )
    (net (code "58") (name "VDD_3V3") (class "Default")
      (node (ref "C1") (pin "2") (pinfunction "2_2") (pintype "passive"))
      (node (ref "C2") (pin "2") (pinfunction "2_2") (pintype "passive"))
      (node (ref "C3") (pin "2") (pinfunction "2_2") (pintype "passive"))
      (node (ref "D2") (pin "C") (pinfunction "C_C") (pintype "passive"))
      (node (ref "D5") (pin "C") (pinfunction "C_C") (pintype "passive"))
      (node (ref "R1") (pin "2") (pinfunction "2_2") (pintype "passive"))
      (node (ref "R10") (pin "1") (pinfunction "1_1") (pintype "passive"))
      (node (ref "R18") (pin "2") (pinfunction "2_2") (pintype "passive"))
      (node (ref "R2") (pin "2") (pinfunction "2_2") (pintype "passive"))
      (node (ref "R38") (pin "1") (pinfunction "1_1") (pintype "passive"))
      (node (ref "U2") (pin "10") (pinfunction "DBVDD_10") (pintype "bidirectional"))
      (node (ref "U2") (pin "8") (pinfunction "DCVDD_8") (pintype "bidirectional"))
      (node (ref "X2") (pin "1") (pinfunction "ENABLE_1") (pintype "bidirectional"))
      (node (ref "X2") (pin "4") (pinfunction "VDD_4") (pintype "bidirectional"))
    )
    (net (code "59") (name "VDD_5V") (class "Default")
      (node (ref "C11") (pin "2") (pinfunction "2_2") (pintype "passive"))
      (node (ref "C12") (pin "2") (pinfunction "2_2") (pintype "passive"))
      (node (ref "C14") (pin "2") (pinfunction "2_2") (pintype "passive"))
      (node (ref "C15") (pin "2") (pinfunction "2_2") (pintype "passive"))
      (node (ref "C22") (pin "2") (pinfunction "2_2") (pintype "passive"))
      (node (ref "C37") (pin "1") (pinfunction "1_1") (pintype "passive"))
      (node (ref "C40") (pin "1") (pinfunction "1_1") (pintype "passive"))
      (node (ref "C8") (pin "1") (pinfunction "1_1") (pintype "passive"))
      (node (ref "C9") (pin "1") (pinfunction "1_1") (pintype "passive"))
      (node (ref "PI") (pin "2") (pinfunction "2_2") (pintype "bidirectional"))
      (node (ref "PI") (pin "4") (pinfunction "4_4") (pintype "bidirectional"))
      (node (ref "R17") (pin "2") (pinfunction "2_2") (pintype "passive"))
      (node (ref "U1") (pin "13") (pinfunction "PVDD1_13") (pintype "output"))
      (node (ref "U1") (pin "4") (pinfunction "PVDD_4") (pintype "input"))
      (node (ref "U1") (pin "5") (pinfunction "MUTE_5") (pintype "input"))
      (node (ref "U1") (pin "6") (pinfunction "VDD_6") (pintype "input"))
      (node (ref "U2") (pin "21") (pinfunction "SPKVDD2_21") (pintype "bidirectional"))
      (node (ref "U2") (pin "26") (pinfunction "SPKVDD1_26") (pintype "bidirectional"))
      (node (ref "U4") (pin "3") (pinfunction "IN_3") (pintype "bidirectional"))
    )
    (net (code "60") (name "VMID") (class "Default")
      (node (ref "C4") (pin "1") (pinfunction "1_1") (pintype "passive"))
      (node (ref "C5") (pin "1") (pinfunction "1_1") (pintype "passive"))
      (node (ref "U2") (pin "27") (pinfunction "VMID_27") (pintype "bidirectional"))
    )
    (net (code "61") (name "unconnected-(PI-Pad1)") (class "Default")
      (node (ref "PI") (pin "1") (pinfunction "1_1") (pintype "bidirectional"))
    )
    (net (code "62") (name "unconnected-(PI-Pad13)") (class "Default")
      (node (ref "PI") (pin "13") (pinfunction "13_13") (pintype "bidirectional"))
    )
    (net (code "63") (name "unconnected-(PI-Pad15)") (class "Default")
      (node (ref "PI") (pin "15") (pinfunction "15_15") (pintype "bidirectional"))
    )
    (net (code "64") (name "unconnected-(PI-Pad16)") (class "Default")
      (node (ref "PI") (pin "16") (pinfunction "16_16") (pintype "bidirectional"))
    )
    (net (code "65") (name "unconnected-(PI-Pad18)") (class "Default")
      (node (ref "PI") (pin "18") (pinfunction "18_18") (pintype "bidirectional"))
    )
    (net (code "66") (name "unconnected-(PI-Pad21)") (class "Default")
      (node (ref "PI") (pin "21") (pinfunction "21_21") (pintype "bidirectional"))
    )
    (net (code "67") (name "unconnected-(PI-Pad22)") (class "Default")
      (node (ref "PI") (pin "22") (pinfunction "22_22") (pintype "bidirectional"))
    )
    (net (code "68") (name "unconnected-(PI-Pad24)") (class "Default")
      (node (ref "PI") (pin "24") (pinfunction "24_24") (pintype "bidirectional"))
    )
    (net (code "69") (name "unconnected-(PI-Pad26)") (class "Default")
      (node (ref "PI") (pin "26") (pinfunction "26_26") (pintype "bidirectional"))
    )
    (net (code "70") (name "unconnected-(PI-Pad27)") (class "Default")
      (node (ref "PI") (pin "27") (pinfunction "27_27") (pintype "bidirectional"))
    )
    (net (code "71") (name "unconnected-(PI-Pad28)") (class "Default")
      (node (ref "PI") (pin "28") (pinfunction "28_28") (pintype "bidirectional"))
    )
    (net (code "72") (name "unconnected-(PI-Pad36)") (class "Default")
      (node (ref "PI") (pin "36") (pinfunction "36_36") (pintype "bidirectional"))
    )
    (net (code "73") (name "unconnected-(U1-+OUT_R-Pad16)") (class "Default")
      (node (ref "U1") (pin "16") (pinfunction "+OUT_R_16") (pintype "output"))
    )
    (net (code "74") (name "unconnected-(U1--OUT_R-Pad14)") (class "Default")
      (node (ref "U1") (pin "14") (pinfunction "-OUT_R_14") (pintype "output"))
    )
    (net (code "75") (name "unconnected-(U1-INR-Pad10)") (class "Default")
      (node (ref "U1") (pin "10") (pinfunction "INR_10") (pintype "output"))
    )
    (net (code "76") (name "unconnected-(U1-NC-Pad9)") (class "Default")
      (node (ref "U1") (pin "9") (pinfunction "NC_9") (pintype "output"))
    )
    (net (code "77") (name "unconnected-(U2-LINPUT3{slash}JD2-Pad2)") (class "Default")
      (node (ref "U2") (pin "2") (pinfunction "LINPUT3/JD2_2") (pintype "bidirectional"))
    )
    (net (code "78") (name "unconnected-(U2-OUT3-Pad30)") (class "Default")
      (node (ref "U2") (pin "30") (pinfunction "OUT3_30") (pintype "bidirectional"))
    )
    (net (code "79") (name "unconnected-(U2-RINPUT3{slash}JD3-Pad7)") (class "Default")
      (node (ref "U2") (pin "7") (pinfunction "RINPUT3/JD3_7") (pintype "bidirectional"))
    )
    (net (code "80") (name "unconnected-(U2-SPK_LN-Pad23)") (class "Default")
      (node (ref "U2") (pin "23") (pinfunction "SPK_LN_23") (pintype "bidirectional"))
    )
    (net (code "81") (name "unconnected-(U2-SPK_LP-Pad25)") (class "Default")
      (node (ref "U2") (pin "25") (pinfunction "SPK_LP_25") (pintype "bidirectional"))
    )
  )
)
